# drive.net
KiCad netlist of a schematic drawn in EAGLE
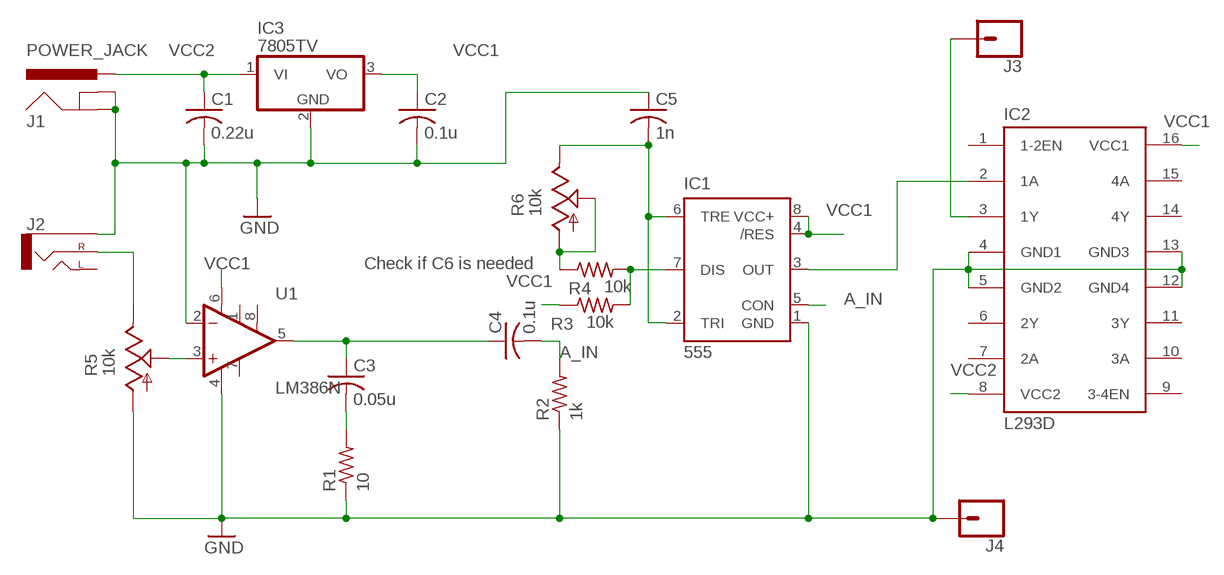
[diagram p0: schematic, sheet 1]

(export (version "E")
  (design (tool "Eeschema 10.0.6"))
  (components
    (comp (ref "C1")
      (value "0.22u")
      (footprint "eagle-import:C025-030X050")
      (libsource (lib "eagle-import") (part "C-US025-030X050"))
    )
    (comp (ref "C2")
      (value "0.1u")
      (footprint "eagle-import:C025-030X050")
      (libsource (lib "eagle-import") (part "C-US025-030X050"))
    )
    (comp (ref "C3")
      (value "0.05u")
      (footprint "eagle-import:C025-030X050")
      (libsource (lib "eagle-import") (part "C-US025-030X050"))
    )
    (comp (ref "C4")
      (value "0.1u")
      (footprint "eagle-import:C025-030X050")
      (libsource (lib "eagle-import") (part "C-US025-030X050"))
    )
    (comp (ref "C5")
      (value "1n")
      (footprint "eagle-import:C025-030X050")
      (libsource (lib "eagle-import") (part "C-US025-030X050"))
    )
    (comp (ref "IC1")
      (value "555")
      (footprint "eagle-import:DIP08")
      (libsource (lib "eagle-import") (part "555P"))
    )
    (comp (ref "IC2")
      (value "L293D")
      (footprint "eagle-import:DIL16")
      (libsource (lib "eagle-import") (part "L293D"))
    )
    (comp (ref "IC3")
      (value "7805TV")
      (footprint "eagle-import:TO220V")
      (libsource (lib "eagle-import") (part "78TV05"))
    )
    (comp (ref "J1")
      (value "POWER_JACK")
      (footprint "eagle-import:POWER_JACK_PTH")
      (libsource (lib "eagle-import") (part "POWER_JACK"))
    )
    (comp (ref "J2")
      (value "AUDIO_JACK_2.5MMSPECIAL_POGO_PINS")
      (footprint "eagle-import:STEREOJACK2.5MM_SPECIAL_POGOPINS")
      (libsource (lib "eagle-import") (part "AUDIO_JACK_2.5MMSPECIAL_POGO_PINS"))
    )
    (comp (ref "J3")
      (value "CONN_01SMTSO-256-ET-0.165DIA")
      (footprint "eagle-import:SMTSO-256-ET-0.165DIA")
      (libsource (lib "eagle-import") (part "CONN_01SMTSO-256-ET-0.165DIA"))
    )
    (comp (ref "J4")
      (value "CONN_01SMTSO-256-ET-0.165DIA")
      (footprint "eagle-import:SMTSO-256-ET-0.165DIA")
      (libsource (lib "eagle-import") (part "CONN_01SMTSO-256-ET-0.165DIA"))
    )
    (comp (ref "R1")
      (value "10")
      (footprint "eagle-import:0207_10")
      (libsource (lib "eagle-import") (part "R-US_0207/10"))
    )
    (comp (ref "R2")
      (value "1k")
      (footprint "eagle-import:0207_10")
      (libsource (lib "eagle-import") (part "R-US_0207/10"))
    )
    (comp (ref "R3")
      (value "10k")
      (footprint "eagle-import:0207_10")
      (libsource (lib "eagle-import") (part "R-US_0207/10"))
    )
    (comp (ref "R4")
      (value "10k")
      (footprint "eagle-import:0207_10")
      (libsource (lib "eagle-import") (part "R-US_0207/10"))
    )
    (comp (ref "R5")
      (value "10k")
      (footprint "eagle-import:CA6V")
      (libsource (lib "eagle-import") (part "TRIM_US-CA6V"))
    )
    (comp (ref "R6")
      (value "10k")
      (footprint "eagle-import:CA6V")
      (libsource (lib "eagle-import") (part "TRIM_US-CA6V"))
    )
    (comp (ref "U1")
      (value "LM386N")
      (footprint "eagle-import:DIP08")
      (libsource (lib "eagle-import") (part "LM386"))
    )
  )
  (nets
    (net (code "1") (name "/A_IN") (class "Default")
      (node (ref "C4") (pin "2") (pinfunction "2_2") (pintype "passive"))
      (node (ref "IC1") (pin "5") (pinfunction "CON_5") (pintype "input"))
      (node (ref "R2") (pin "2") (pinfunction "2_2") (pintype "passive"))
    )
    (net (code "2") (name "/VCC1") (class "Default")
      (node (ref "C2") (pin "1") (pinfunction "1_1") (pintype "passive"))
      (node (ref "IC1") (pin "4") (pinfunction "/RES_4") (pintype "input"))
      (node (ref "IC1") (pin "8") (pinfunction "VCC+_8") (pintype "power_in"))
      (node (ref "IC2") (pin "16") (pinfunction "VCC1_16") (pintype "power_in"))
      (node (ref "IC3") (pin "3") (pinfunction "VO_3") (pintype "passive"))
      (node (ref "R3") (pin "1") (pinfunction "1_1") (pintype "passive"))
      (node (ref "U1") (pin "6") (pinfunction "V+_6") (pintype "power_in"))
    )
    (net (code "3") (name "/VCC2") (class "Default")
      (node (ref "C1") (pin "1") (pinfunction "1_1") (pintype "passive"))
      (node (ref "IC2") (pin "8") (pinfunction "VCC2_8") (pintype "power_in"))
      (node (ref "IC3") (pin "1") (pinfunction "VI_1") (pintype "input"))
      (node (ref "J1") (pin "PWR") (pinfunction "PWR_PWR") (pintype "bidirectional"))
    )
    (net (code "4") (name "GND") (class "Default")
      (node (ref "C1") (pin "2") (pinfunction "2_2") (pintype "passive"))
      (node (ref "C2") (pin "2") (pinfunction "2_2") (pintype "passive"))
      (node (ref "C5") (pin "1") (pinfunction "1_1") (pintype "passive"))
      (node (ref "IC1") (pin "1") (pinfunction "GND_1") (pintype "power_in"))
      (node (ref "IC2") (pin "12") (pinfunction "GND4_12") (pintype "power_in"))
      (node (ref "IC2") (pin "13") (pinfunction "GND3_13") (pintype "power_in"))
      (node (ref "IC2") (pin "4") (pinfunction "GND1_4") (pintype "power_in"))
      (node (ref "IC2") (pin "5") (pinfunction "GND2_5") (pintype "power_in"))
      (node (ref "IC3") (pin "2") (pinfunction "GND_2") (pintype "passive"))
      (node (ref "J1") (pin "GND") (pinfunction "GND_GND") (pintype "bidirectional"))
      (node (ref "J1") (pin "GNDBREAK") (pinfunction "GNDBREAK_GNDBREAK") (pintype "bidirectional"))
      (node (ref "J2") (pin "RING1") (pinfunction "SLEEVE_RING1") (pintype "bidirectional"))
      (node (ref "J4") (pin "P$1") (pinfunction "1_P$1") (pintype "passive"))
      (node (ref "R1") (pin "1") (pinfunction "1_1") (pintype "passive"))
      (node (ref "R2") (pin "1") (pinfunction "1_1") (pintype "passive"))
      (node (ref "R5") (pin "A") (pinfunction "A_A") (pintype "passive"))
      (node (ref "U1") (pin "2") (pinfunction "-IN_2") (pintype "input"))
      (node (ref "U1") (pin "4") (pinfunction "V-_4") (pintype "power_in"))
    )
    (net (code "5") (name "Net-(C3-Pad2)") (class "Default")
      (node (ref "C3") (pin "2") (pinfunction "2_2") (pintype "passive"))
      (node (ref "R1") (pin "2") (pinfunction "2_2") (pintype "passive"))
    )
    (net (code "6") (name "Net-(IC1-DIS)") (class "Default")
      (node (ref "IC1") (pin "7") (pinfunction "DIS_7") (pintype "input"))
      (node (ref "R3") (pin "2") (pinfunction "2_2") (pintype "passive"))
      (node (ref "R4") (pin "2") (pinfunction "2_2") (pintype "passive"))
    )
    (net (code "7") (name "Net-(IC1-OUT)") (class "Default")
      (node (ref "IC1") (pin "3") (pinfunction "OUT_3") (pintype "output"))
      (node (ref "IC2") (pin "2") (pinfunction "1A_2") (pintype "input"))
    )
    (net (code "8") (name "Net-(IC1-TRE)") (class "Default")
      (node (ref "C5") (pin "2") (pinfunction "2_2") (pintype "passive"))
      (node (ref "IC1") (pin "2") (pinfunction "TRI_2") (pintype "input"))
      (node (ref "IC1") (pin "6") (pinfunction "TRE_6") (pintype "input"))
      (node (ref "R6") (pin "E") (pinfunction "E_E") (pintype "passive"))
    )
    (net (code "9") (name "Net-(IC2-1Y)") (class "Default")
      (node (ref "IC2") (pin "3") (pinfunction "1Y_3") (pintype "output"))
      (node (ref "J3") (pin "P$1") (pinfunction "1_P$1") (pintype "passive"))
    )
    (net (code "10") (name "Net-(J2-RIGHT)") (class "Default")
      (node (ref "J2") (pin "TIP") (pinfunction "RIGHT_TIP") (pintype "bidirectional"))
      (node (ref "R5") (pin "E") (pinfunction "E_E") (pintype "passive"))
    )
    (net (code "11") (name "Net-(R4-Pad1)") (class "Default")
      (node (ref "R4") (pin "1") (pinfunction "1_1") (pintype "passive"))
      (node (ref "R6") (pin "A") (pinfunction "A_A") (pintype "passive"))
      (node (ref "R6") (pin "S") (pinfunction "S_S") (pintype "passive"))
    )
    (net (code "12") (name "Net-(U1-+IN)") (class "Default")
      (node (ref "R5") (pin "S") (pinfunction "S_S") (pintype "passive"))
      (node (ref "U1") (pin "3") (pinfunction "+IN_3") (pintype "input"))
    )
    (net (code "13") (name "Net-(U1-OUT)") (class "Default")
      (node (ref "C3") (pin "1") (pinfunction "1_1") (pintype "passive"))
      (node (ref "C4") (pin "1") (pinfunction "1_1") (pintype "passive"))
      (node (ref "U1") (pin "5") (pinfunction "OUT_5") (pintype "output"))
    )
    (net (code "14") (name "unconnected-(IC2-1-2EN-Pad1)") (class "Default")
      (node (ref "IC2") (pin "1") (pinfunction "1-2EN_1") (pintype "input"))
    )
    (net (code "15") (name "unconnected-(IC2-2A-Pad7)") (class "Default")
      (node (ref "IC2") (pin "7") (pinfunction "2A_7") (pintype "input"))
    )
    (net (code "16") (name "unconnected-(IC2-2Y-Pad6)") (class "Default")
      (node (ref "IC2") (pin "6") (pinfunction "2Y_6") (pintype "output"))
    )
    (net (code "17") (name "unconnected-(IC2-3-4EN-Pad9)") (class "Default")
      (node (ref "IC2") (pin "9") (pinfunction "3-4EN_9") (pintype "input"))
    )
    (net (code "18") (name "unconnected-(IC2-3A-Pad10)") (class "Default")
      (node (ref "IC2") (pin "10") (pinfunction "3A_10") (pintype "input"))
    )
    (net (code "19") (name "unconnected-(IC2-3Y-Pad11)") (class "Default")
      (node (ref "IC2") (pin "11") (pinfunction "3Y_11") (pintype "output"))
    )
    (net (code "20") (name "unconnected-(IC2-4A-Pad15)") (class "Default")
      (node (ref "IC2") (pin "15") (pinfunction "4A_15") (pintype "input"))
    )
    (net (code "21") (name "unconnected-(IC2-4Y-Pad14)") (class "Default")
      (node (ref "IC2") (pin "14") (pinfunction "4Y_14") (pintype "output"))
    )
    (net (code "22") (name "unconnected-(J2-LEFT-PadSHIELD)") (class "Default")
      (node (ref "J2") (pin "SHIELD") (pinfunction "LEFT_SHIELD") (pintype "bidirectional"))
    )
    (net (code "23") (name "unconnected-(U1-BP-Pad7)") (class "Default")
      (node (ref "U1") (pin "7") (pinfunction "BP_7") (pintype "bidirectional"))
    )
    (net (code "24") (name "unconnected-(U1-GAIN-Pad1)") (class "Default")
      (node (ref "U1") (pin "1") (pinfunction "GAIN_1") (pintype "bidirectional"))
    )
    (net (code "25") (name "unconnected-(U1-GAIN-Pad8)") (class "Default")
      (node (ref "U1") (pin "8") (pinfunction "GAIN_8") (pintype "bidirectional"))
    )
  )
)
